# Regn_Weather_Station.net
KiCad netlist of a schematic drawn in EAGLE
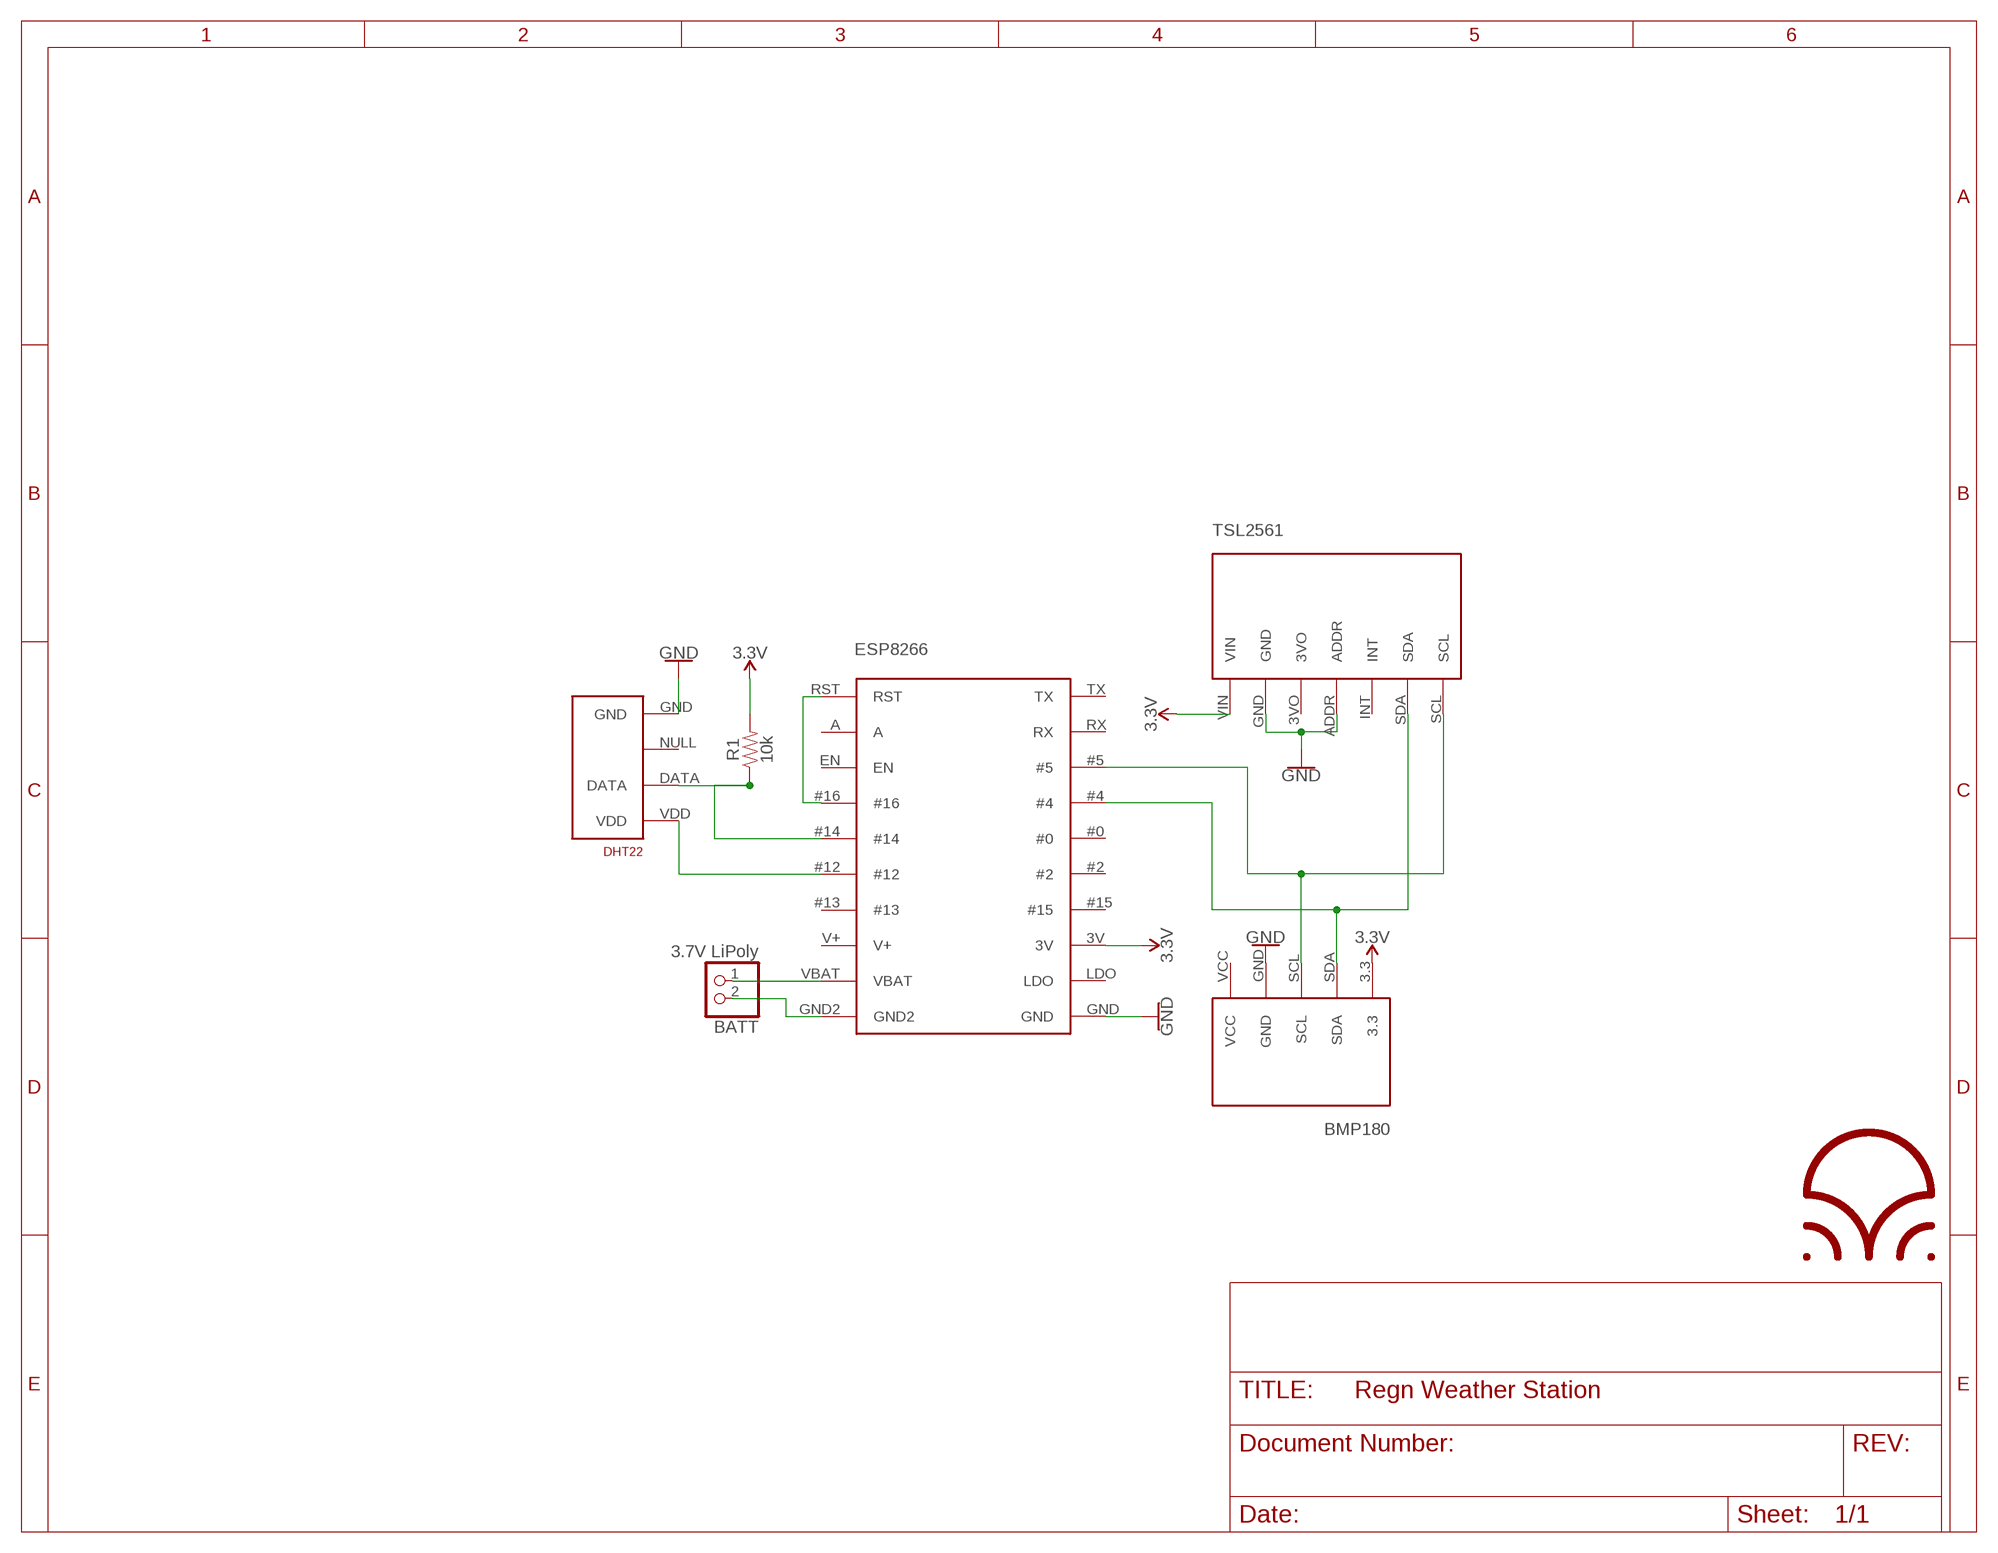
[diagram p0: schematic, sheet 1]

(export (version "E")
  (design (tool "Eeschema 10.0.6"))
  (components
    (comp (ref "BATT")
      (value "3.7V LiPoly")
      (footprint "eagle-import:JST-PH-2-SMT")
      (libsource (lib "eagle-import") (part "JST_2PIN-SMT"))
    )
    (comp (ref "BMP180")
      (value "BMP180")
      (footprint "eagle-import:BMP180")
      (libsource (lib "eagle-import") (part "BMP180"))
    )
    (comp (ref "DHT22")
      (value "RHT03_DHT-22_AM2302WIRED")
      (footprint "eagle-import:AM2302")
      (libsource (lib "eagle-import") (part "RHT03_DHT-22_AM2302WIRED"))
    )
    (comp (ref "ESP8266")
      (value "ESP8266HUZZAH")
      (footprint "eagle-import:ESP8266HUZZAH")
      (libsource (lib "eagle-import") (part "ESP8266HUZZAH"))
    )
    (comp (ref "R1")
      (value "10k")
      (footprint "eagle-import:AXIAL-0.3")
      (libsource (lib "eagle-import") (part "10KOHM-HORIZ-1/4W-1%"))
    )
    (comp (ref "TSL2561")
      (value "TSL2561")
      (footprint "eagle-import:TSL2561")
      (libsource (lib "eagle-import") (part "TSL2561"))
    )
  )
  (nets
    (net (code "1") (name "/V+") (class "Default")
      (node (ref "ESP8266") (pin "V+") (pinfunction "V+_V+") (pintype "power_in"))
    )
    (net (code "2") (name "/VCC") (class "Default")
      (node (ref "BMP180") (pin "VCC") (pinfunction "VCC_VCC") (pintype "power_in"))
    )
    (net (code "3") (name "3.3V") (class "Default")
      (node (ref "BMP180") (pin "3.3") (pinfunction "3.3_3.3") (pintype "power_in"))
      (node (ref "ESP8266") (pin "3V") (pinfunction "3V_3V") (pintype "bidirectional"))
      (node (ref "R1") (pin "P$2") (pinfunction "2_P$2") (pintype "passive"))
      (node (ref "TSL2561") (pin "VIN") (pinfunction "VIN_VIN") (pintype "power_in"))
    )
    (net (code "4") (name "GND") (class "Default")
      (node (ref "BMP180") (pin "GND") (pinfunction "GND_GND") (pintype "bidirectional"))
      (node (ref "DHT22") (pin "GND") (pinfunction "GND_GND") (pintype "power_in"))
      (node (ref "ESP8266") (pin "GND") (pinfunction "GND_GND") (pintype "bidirectional"))
      (node (ref "TSL2561") (pin "ADDR") (pinfunction "ADDR_ADDR") (pintype "bidirectional"))
      (node (ref "TSL2561") (pin "GND") (pinfunction "GND_GND") (pintype "bidirectional"))
    )
    (net (code "5") (name "Net-(BATT-1)") (class "Default")
      (node (ref "BATT") (pin "2") (pinfunction "1_2") (pintype "passive"))
      (node (ref "ESP8266") (pin "GND2") (pinfunction "GND2_GND2") (pintype "bidirectional"))
    )
    (net (code "6") (name "Net-(BATT-2)") (class "Default")
      (node (ref "BATT") (pin "1") (pinfunction "2_1") (pintype "passive"))
      (node (ref "ESP8266") (pin "VBAT") (pinfunction "VBAT_VBAT") (pintype "power_in"))
    )
    (net (code "7") (name "Net-(BMP180-PadSCL)") (class "Default")
      (node (ref "BMP180") (pin "SCL") (pinfunction "SCL_SCL") (pintype "bidirectional"))
      (node (ref "ESP8266") (pin "#5") (pinfunction "#5_#5") (pintype "bidirectional"))
      (node (ref "TSL2561") (pin "SCL") (pinfunction "SCL_SCL") (pintype "bidirectional"))
    )
    (net (code "8") (name "Net-(BMP180-PadSDA)") (class "Default")
      (node (ref "BMP180") (pin "SDA") (pinfunction "SDA_SDA") (pintype "bidirectional"))
      (node (ref "ESP8266") (pin "#4") (pinfunction "#4_#4") (pintype "bidirectional"))
      (node (ref "TSL2561") (pin "SDA") (pinfunction "SDA_SDA") (pintype "bidirectional"))
    )
    (net (code "9") (name "Net-(DHT22-PadVDD)") (class "Default")
      (node (ref "DHT22") (pin "VDD") (pinfunction "VDD_VDD") (pintype "power_in"))
      (node (ref "ESP8266") (pin "#12") (pinfunction "#12_#12") (pintype "bidirectional"))
    )
    (net (code "10") (name "Net-(ESP8266-Pad#16)") (class "Default")
      (node (ref "ESP8266") (pin "#16") (pinfunction "#16_#16") (pintype "bidirectional"))
      (node (ref "ESP8266") (pin "RST") (pinfunction "RST_RST") (pintype "bidirectional"))
    )
    (net (code "11") (name "Net-(R1-1)") (class "Default")
      (node (ref "DHT22") (pin "DATA") (pinfunction "DATA_DATA") (pintype "bidirectional"))
      (node (ref "ESP8266") (pin "#14") (pinfunction "#14_#14") (pintype "bidirectional"))
      (node (ref "R1") (pin "P$1") (pinfunction "1_P$1") (pintype "passive"))
    )
    (net (code "12") (name "unconnected-(DHT22-PadNULL)") (class "Default")
      (node (ref "DHT22") (pin "NULL") (pinfunction "NULL_NULL") (pintype "no_connect"))
    )
    (net (code "13") (name "unconnected-(ESP8266-Pad#0)") (class "Default")
      (node (ref "ESP8266") (pin "#0") (pinfunction "#0_#0") (pintype "bidirectional"))
    )
    (net (code "14") (name "unconnected-(ESP8266-Pad#2)") (class "Default")
      (node (ref "ESP8266") (pin "#2") (pinfunction "#2_#2") (pintype "bidirectional"))
    )
    (net (code "15") (name "unconnected-(ESP8266-Pad#13)") (class "Default")
      (node (ref "ESP8266") (pin "#13") (pinfunction "#13_#13") (pintype "bidirectional"))
    )
    (net (code "16") (name "unconnected-(ESP8266-Pad#15)") (class "Default")
      (node (ref "ESP8266") (pin "#15") (pinfunction "#15_#15") (pintype "bidirectional"))
    )
    (net (code "17") (name "unconnected-(ESP8266-PadA)") (class "Default")
      (node (ref "ESP8266") (pin "A") (pinfunction "A_A") (pintype "bidirectional"))
    )
    (net (code "18") (name "unconnected-(ESP8266-PadEN)") (class "Default")
      (node (ref "ESP8266") (pin "EN") (pinfunction "EN_EN") (pintype "bidirectional"))
    )
    (net (code "19") (name "unconnected-(ESP8266-PadLDO)") (class "Default")
      (node (ref "ESP8266") (pin "LDO") (pinfunction "LDO_LDO") (pintype "bidirectional"))
    )
    (net (code "20") (name "unconnected-(ESP8266-PadRX)") (class "Default")
      (node (ref "ESP8266") (pin "RX") (pinfunction "RX_RX") (pintype "bidirectional"))
    )
    (net (code "21") (name "unconnected-(ESP8266-PadTX)") (class "Default")
      (node (ref "ESP8266") (pin "TX") (pinfunction "TX_TX") (pintype "bidirectional"))
    )
    (net (code "22") (name "unconnected-(TSL2561-Pad3VO)") (class "Default")
      (node (ref "TSL2561") (pin "3VO") (pinfunction "3VO_3VO") (pintype "bidirectional"))
    )
    (net (code "23") (name "unconnected-(TSL2561-PadINT)") (class "Default")
      (node (ref "TSL2561") (pin "INT") (pinfunction "INT_INT") (pintype "bidirectional"))
    )
  )
)
